# leitorEncoder.net
KiCad netlist of a schematic drawn in EAGLE
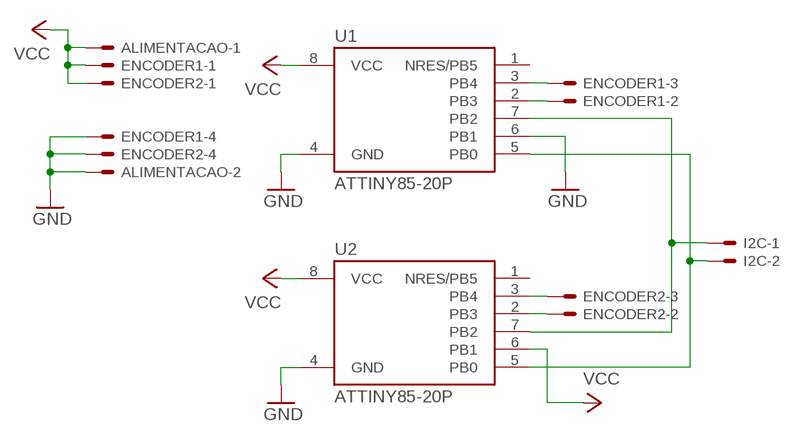
[diagram p0: schematic, sheet 1]

(export (version "E")
  (design (tool "Eeschema 10.0.6"))
  (components
    (comp (ref "ALIMENTACAO")
      (value "CONN_0227-2021")
      (footprint "eagle-import:6410-02")
      (libsource (lib "eagle-import") (part "CONN_0227-2021"))
    )
    (comp (ref "ENCODER1")
      (value "CONN_0427-2041")
      (footprint "eagle-import:6410-04")
      (libsource (lib "eagle-import") (part "CONN_0427-2041"))
    )
    (comp (ref "ENCODER2")
      (value "CONN_0427-2041")
      (footprint "eagle-import:6410-04")
      (libsource (lib "eagle-import") (part "CONN_0427-2041"))
    )
    (comp (ref "I2C")
      (value "CONN_0227-2021")
      (footprint "eagle-import:6410-02")
      (libsource (lib "eagle-import") (part "CONN_0227-2021"))
    )
    (comp (ref "U1")
      (value "ATTINY85-20P")
      (footprint "eagle-import:PDIP08_300MIL")
      (libsource (lib "eagle-import") (part "ATTINY85P-20"))
    )
    (comp (ref "U2")
      (value "ATTINY85-20P")
      (footprint "eagle-import:PDIP08_300MIL")
      (libsource (lib "eagle-import") (part "ATTINY85P-20"))
    )
  )
  (nets
    (net (code "1") (name "GND") (class "Default")
      (node (ref "ALIMENTACAO") (pin "2") (pinfunction "S_2") (pintype "passive"))
      (node (ref "ENCODER1") (pin "4") (pinfunction "S_4") (pintype "passive"))
      (node (ref "ENCODER2") (pin "4") (pinfunction "S_4") (pintype "passive"))
      (node (ref "U1") (pin "4") (pinfunction "GND_4") (pintype "power_in"))
      (node (ref "U1") (pin "6") (pinfunction "PB1_6") (pintype "bidirectional"))
      (node (ref "U2") (pin "4") (pinfunction "GND_4") (pintype "power_in"))
    )
    (net (code "2") (name "Net-(ENCODER1B-S)") (class "Default")
      (node (ref "ENCODER1") (pin "2") (pinfunction "S_2") (pintype "passive"))
      (node (ref "U1") (pin "2") (pinfunction "PB3_2") (pintype "bidirectional"))
    )
    (net (code "3") (name "Net-(ENCODER1C-S)") (class "Default")
      (node (ref "ENCODER1") (pin "3") (pinfunction "S_3") (pintype "passive"))
      (node (ref "U1") (pin "3") (pinfunction "PB4_3") (pintype "bidirectional"))
    )
    (net (code "4") (name "Net-(ENCODER2B-S)") (class "Default")
      (node (ref "ENCODER2") (pin "2") (pinfunction "S_2") (pintype "passive"))
      (node (ref "U2") (pin "2") (pinfunction "PB3_2") (pintype "bidirectional"))
    )
    (net (code "5") (name "Net-(ENCODER2C-S)") (class "Default")
      (node (ref "ENCODER2") (pin "3") (pinfunction "S_3") (pintype "passive"))
      (node (ref "U2") (pin "3") (pinfunction "PB4_3") (pintype "bidirectional"))
    )
    (net (code "6") (name "Net-(I2CA-S)") (class "Default")
      (node (ref "I2C") (pin "1") (pinfunction "S_1") (pintype "passive"))
      (node (ref "U1") (pin "7") (pinfunction "PB2_7") (pintype "bidirectional"))
      (node (ref "U2") (pin "7") (pinfunction "PB2_7") (pintype "bidirectional"))
    )
    (net (code "7") (name "Net-(I2CB-S)") (class "Default")
      (node (ref "I2C") (pin "2") (pinfunction "S_2") (pintype "passive"))
      (node (ref "U1") (pin "5") (pinfunction "PB0_5") (pintype "bidirectional"))
      (node (ref "U2") (pin "5") (pinfunction "PB0_5") (pintype "bidirectional"))
    )
    (net (code "8") (name "VCC") (class "Default")
      (node (ref "ALIMENTACAO") (pin "1") (pinfunction "S_1") (pintype "passive"))
      (node (ref "ENCODER1") (pin "1") (pinfunction "S_1") (pintype "passive"))
      (node (ref "ENCODER2") (pin "1") (pinfunction "S_1") (pintype "passive"))
      (node (ref "U1") (pin "8") (pinfunction "VCC_8") (pintype "power_in"))
      (node (ref "U2") (pin "6") (pinfunction "PB1_6") (pintype "bidirectional"))
      (node (ref "U2") (pin "8") (pinfunction "VCC_8") (pintype "power_in"))
    )
    (net (code "9") (name "unconnected-(U1-NRES{slash}PB5-Pad1)") (class "Default")
      (node (ref "U1") (pin "1") (pinfunction "NRES/PB5_1") (pintype "bidirectional"))
    )
    (net (code "10") (name "unconnected-(U2-NRES{slash}PB5-Pad1)") (class "Default")
      (node (ref "U2") (pin "1") (pinfunction "NRES/PB5_1") (pintype "bidirectional"))
    )
  )
)
